# main.net
KiCad netlist of a schematic drawn in EAGLE
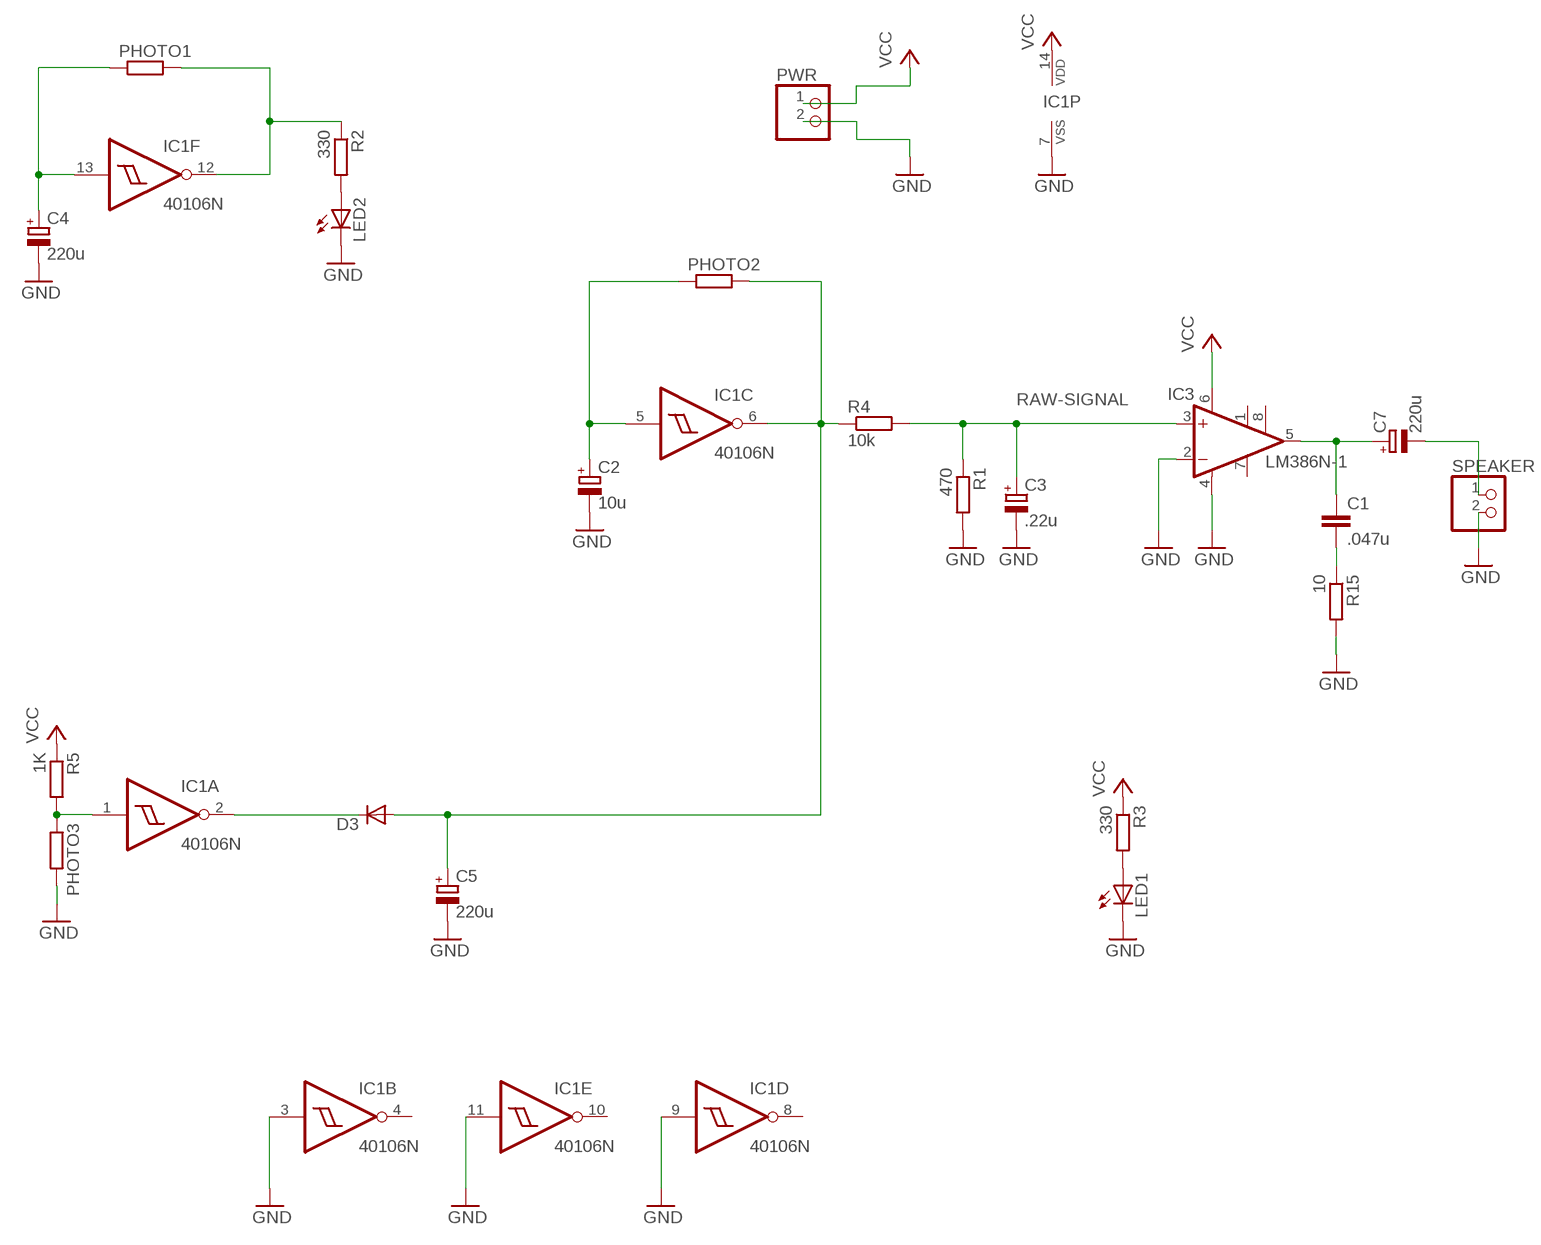
[diagram p0: schematic, sheet 1]

(export (version "E")
  (design (tool "Eeschema 10.0.6"))
  (components
    (comp (ref "C1")
      (value ".047u")
      (footprint "eagle-import:C025-025X050")
      (libsource (lib "eagle-import") (part "C-EU025-025X050"))
    )
    (comp (ref "C2")
      (value "10u")
      (footprint "eagle-import:TT2D6")
      (libsource (lib "eagle-import") (part "CPOL-EUTT2D6"))
    )
    (comp (ref "C3")
      (value ".22u")
      (footprint "eagle-import:TT2D6")
      (libsource (lib "eagle-import") (part "CPOL-EUTT2D6"))
    )
    (comp (ref "C4")
      (value "220u")
      (footprint "eagle-import:TT2D6")
      (libsource (lib "eagle-import") (part "CPOL-EUTT2D6"))
    )
    (comp (ref "C5")
      (value "220u")
      (footprint "eagle-import:TT2D6")
      (libsource (lib "eagle-import") (part "CPOL-EUTT2D6"))
    )
    (comp (ref "C7")
      (value "220u")
      (footprint "eagle-import:TT2D6")
      (libsource (lib "eagle-import") (part "CPOL-EUTT2D6"))
    )
    (comp (ref "D3")
      (value "DIODE-DO35-10")
      (footprint "eagle-import:DO35-10")
      (libsource (lib "eagle-import") (part "DIODE-DO35-10"))
    )
    (comp (ref "IC1")
      (value "40106N")
      (footprint "eagle-import:DIL14")
      (libsource (lib "eagle-import") (part "40106N"))
    )
    (comp (ref "IC3")
      (value "LM386N-1")
      (footprint "eagle-import:DIL08")
      (libsource (lib "eagle-import") (part "LM386?-N1"))
    )
    (comp (ref "LED1")
      (value "LED5MM")
      (footprint "eagle-import:LED5MM")
      (libsource (lib "eagle-import") (part "LED5MM"))
    )
    (comp (ref "LED2")
      (value "LED5MM")
      (footprint "eagle-import:LED5MM")
      (libsource (lib "eagle-import") (part "LED5MM"))
    )
    (comp (ref "PHOTO1")
      (value "R-EU_0207/5V")
      (footprint "eagle-import:0207_5V")
      (libsource (lib "eagle-import") (part "R-EU_0207/5V"))
    )
    (comp (ref "PHOTO2")
      (value "R-EU_0207/5V")
      (footprint "eagle-import:0207_5V")
      (libsource (lib "eagle-import") (part "R-EU_0207/5V"))
    )
    (comp (ref "PHOTO3")
      (value "R-EU_0207/5V")
      (footprint "eagle-import:0207_5V")
      (libsource (lib "eagle-import") (part "R-EU_0207/5V"))
    )
    (comp (ref "PWR")
      (value "PINHD-1X2STRAIGHT")
      (footprint "eagle-import:1X02")
      (libsource (lib "eagle-import") (part "PINHD-1X2STRAIGHT"))
    )
    (comp (ref "R1")
      (value "470")
      (footprint "eagle-import:0207_10")
      (libsource (lib "eagle-import") (part "R-EU_0207/10"))
    )
    (comp (ref "R2")
      (value "330")
      (footprint "eagle-import:0207_10")
      (libsource (lib "eagle-import") (part "R-EU_0207/10"))
    )
    (comp (ref "R3")
      (value "330")
      (footprint "eagle-import:0207_10")
      (libsource (lib "eagle-import") (part "R-EU_0207/10"))
    )
    (comp (ref "R4")
      (value "10k")
      (footprint "eagle-import:0207_10")
      (libsource (lib "eagle-import") (part "R-EU_0207/10"))
    )
    (comp (ref "R5")
      (value "1K")
      (footprint "eagle-import:0207_10")
      (libsource (lib "eagle-import") (part "R-EU_0207/10"))
    )
    (comp (ref "R15")
      (value "10")
      (footprint "eagle-import:0207_10")
      (libsource (lib "eagle-import") (part "R-EU_0207/10"))
    )
    (comp (ref "SPEAKER")
      (value "PINHD-1X2STRAIGHT")
      (footprint "eagle-import:1X02")
      (libsource (lib "eagle-import") (part "PINHD-1X2STRAIGHT"))
    )
  )
  (nets
    (net (code "1") (name "/RAW-SIGNAL") (class "Default")
      (node (ref "C3") (pin "+") (pinfunction "+_+") (pintype "passive"))
      (node (ref "IC3") (pin "3") (pinfunction "+IN_3") (pintype "input"))
      (node (ref "R1") (pin "1") (pinfunction "1_1") (pintype "passive"))
      (node (ref "R4") (pin "2") (pinfunction "2_2") (pintype "passive"))
    )
    (net (code "2") (name "GND") (class "Default")
      (node (ref "C2") (pin "-") (pinfunction "-_-") (pintype "passive"))
      (node (ref "C3") (pin "-") (pinfunction "-_-") (pintype "passive"))
      (node (ref "C4") (pin "-") (pinfunction "-_-") (pintype "passive"))
      (node (ref "C5") (pin "-") (pinfunction "-_-") (pintype "passive"))
      (node (ref "IC1") (pin "11") (pinfunction "I_11") (pintype "input"))
      (node (ref "IC1") (pin "3") (pinfunction "I_3") (pintype "input"))
      (node (ref "IC1") (pin "7") (pinfunction "VSS_7") (pintype "power_in"))
      (node (ref "IC1") (pin "9") (pinfunction "I_9") (pintype "input"))
      (node (ref "IC3") (pin "2") (pinfunction "-IN_2") (pintype "input"))
      (node (ref "IC3") (pin "4") (pinfunction "GND_4") (pintype "power_in"))
      (node (ref "LED1") (pin "K") (pinfunction "C_K") (pintype "passive"))
      (node (ref "LED2") (pin "K") (pinfunction "C_K") (pintype "passive"))
      (node (ref "PHOTO3") (pin "2") (pinfunction "2_2") (pintype "passive"))
      (node (ref "PWR") (pin "2") (pinfunction "2_2") (pintype "passive"))
      (node (ref "R1") (pin "2") (pinfunction "2_2") (pintype "passive"))
      (node (ref "R15") (pin "2") (pinfunction "2_2") (pintype "passive"))
      (node (ref "SPEAKER") (pin "2") (pinfunction "2_2") (pintype "passive"))
    )
    (net (code "3") (name "Net-(C1-Pad2)") (class "Default")
      (node (ref "C1") (pin "2") (pinfunction "2_2") (pintype "passive"))
      (node (ref "R15") (pin "1") (pinfunction "1_1") (pintype "passive"))
    )
    (net (code "4") (name "Net-(C7-Pad-)") (class "Default")
      (node (ref "C7") (pin "-") (pinfunction "-_-") (pintype "passive"))
      (node (ref "SPEAKER") (pin "1") (pinfunction "1_1") (pintype "passive"))
    )
    (net (code "5") (name "Net-(IC1A-I)") (class "Default")
      (node (ref "IC1") (pin "1") (pinfunction "I_1") (pintype "input"))
      (node (ref "PHOTO3") (pin "1") (pinfunction "1_1") (pintype "passive"))
      (node (ref "R5") (pin "2") (pinfunction "2_2") (pintype "passive"))
    )
    (net (code "6") (name "Net-(IC1A-O)") (class "Default")
      (node (ref "D3") (pin "C") (pinfunction "C_C") (pintype "passive"))
      (node (ref "IC1") (pin "2") (pinfunction "O_2") (pintype "output"))
    )
    (net (code "7") (name "Net-(IC1C-I)") (class "Default")
      (node (ref "C2") (pin "+") (pinfunction "+_+") (pintype "passive"))
      (node (ref "IC1") (pin "5") (pinfunction "I_5") (pintype "input"))
      (node (ref "PHOTO2") (pin "1") (pinfunction "1_1") (pintype "passive"))
    )
    (net (code "8") (name "Net-(IC1C-O)") (class "Default")
      (node (ref "C5") (pin "+") (pinfunction "+_+") (pintype "passive"))
      (node (ref "D3") (pin "A") (pinfunction "A_A") (pintype "passive"))
      (node (ref "IC1") (pin "6") (pinfunction "O_6") (pintype "output"))
      (node (ref "PHOTO2") (pin "2") (pinfunction "2_2") (pintype "passive"))
      (node (ref "R4") (pin "1") (pinfunction "1_1") (pintype "passive"))
    )
    (net (code "9") (name "Net-(IC1F-I)") (class "Default")
      (node (ref "C4") (pin "+") (pinfunction "+_+") (pintype "passive"))
      (node (ref "IC1") (pin "13") (pinfunction "I_13") (pintype "input"))
      (node (ref "PHOTO1") (pin "1") (pinfunction "1_1") (pintype "passive"))
    )
    (net (code "10") (name "Net-(IC1F-O)") (class "Default")
      (node (ref "IC1") (pin "12") (pinfunction "O_12") (pintype "output"))
      (node (ref "PHOTO1") (pin "2") (pinfunction "2_2") (pintype "passive"))
      (node (ref "R2") (pin "1") (pinfunction "1_1") (pintype "passive"))
    )
    (net (code "11") (name "Net-(IC3-OUT)") (class "Default")
      (node (ref "C1") (pin "1") (pinfunction "1_1") (pintype "passive"))
      (node (ref "C7") (pin "+") (pinfunction "+_+") (pintype "passive"))
      (node (ref "IC3") (pin "5") (pinfunction "OUT_5") (pintype "output"))
    )
    (net (code "12") (name "Net-(LED1-PadA)") (class "Default")
      (node (ref "LED1") (pin "A") (pinfunction "A_A") (pintype "passive"))
      (node (ref "R3") (pin "2") (pinfunction "2_2") (pintype "passive"))
    )
    (net (code "13") (name "Net-(LED2-PadA)") (class "Default")
      (node (ref "LED2") (pin "A") (pinfunction "A_A") (pintype "passive"))
      (node (ref "R2") (pin "2") (pinfunction "2_2") (pintype "passive"))
    )
    (net (code "14") (name "VCC") (class "Default")
      (node (ref "IC1") (pin "14") (pinfunction "VDD_14") (pintype "power_in"))
      (node (ref "IC3") (pin "6") (pinfunction "VS_6") (pintype "power_in"))
      (node (ref "PWR") (pin "1") (pinfunction "1_1") (pintype "passive"))
      (node (ref "R3") (pin "1") (pinfunction "1_1") (pintype "passive"))
      (node (ref "R5") (pin "1") (pinfunction "1_1") (pintype "passive"))
    )
    (net (code "15") (name "unconnected-(IC1B-O-Pad4)") (class "Default")
      (node (ref "IC1") (pin "4") (pinfunction "O_4") (pintype "output"))
    )
    (net (code "16") (name "unconnected-(IC1D-O-Pad8)") (class "Default")
      (node (ref "IC1") (pin "8") (pinfunction "O_8") (pintype "output"))
    )
    (net (code "17") (name "unconnected-(IC1E-O-Pad10)") (class "Default")
      (node (ref "IC1") (pin "10") (pinfunction "O_10") (pintype "output"))
    )
    (net (code "18") (name "unconnected-(IC3-BYPASS-Pad7)") (class "Default")
      (node (ref "IC3") (pin "7") (pinfunction "BYPASS_7") (pintype "passive"))
    )
    (net (code "19") (name "unconnected-(IC3-GAIN-Pad1)") (class "Default")
      (node (ref "IC3") (pin "1") (pinfunction "GAIN_1") (pintype "passive"))
    )
    (net (code "20") (name "unconnected-(IC3-GAIN-Pad8)") (class "Default")
      (node (ref "IC3") (pin "8") (pinfunction "GAIN_8") (pintype "passive"))
    )
  )
)
